# TestRig2.net
KiCad netlist of a schematic drawn in EAGLE
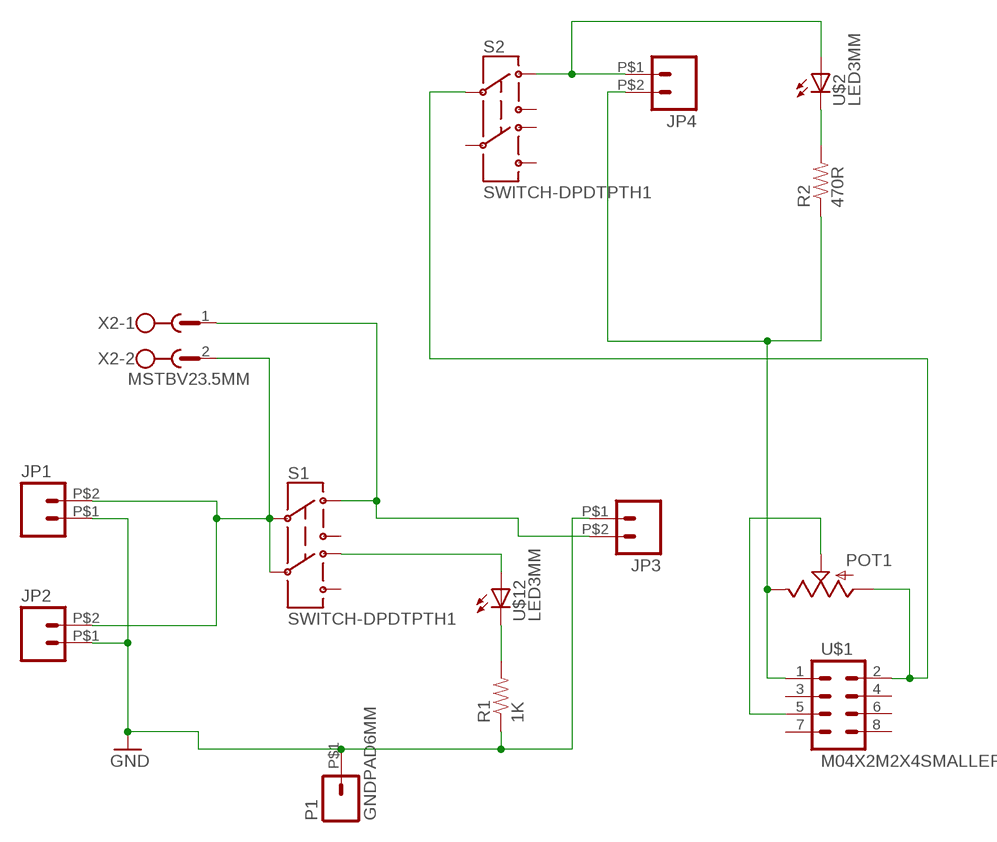
[diagram p0: schematic, sheet 1]

(export (version "E")
  (design (tool "Eeschema 10.0.6"))
  (components
    (comp (ref "JP1")
      (value "M02PTH2")
      (footprint "eagle-import:1X02_BIG")
      (libsource (lib "eagle-import") (part "M02PTH2"))
    )
    (comp (ref "JP2")
      (value "M02PTH2")
      (footprint "eagle-import:1X02_BIG")
      (libsource (lib "eagle-import") (part "M02PTH2"))
    )
    (comp (ref "JP3")
      (value "M02PTH2")
      (footprint "eagle-import:1X02_BIG")
      (libsource (lib "eagle-import") (part "M02PTH2"))
    )
    (comp (ref "JP4")
      (value "M02PTH2")
      (footprint "eagle-import:1X02_BIG")
      (libsource (lib "eagle-import") (part "M02PTH2"))
    )
    (comp (ref "P1")
      (value "GNDPAD6MM")
      (footprint "eagle-import:3.2MMPAD6MM")
      (libsource (lib "eagle-import") (part "GNDPAD6MM"))
    )
    (comp (ref "POT1")
      (value "POT")
      (footprint "eagle-import:ALPS_POT")
      (libsource (lib "eagle-import") (part "POT"))
    )
    (comp (ref "R1")
      (value "1K")
      (footprint "eagle-import:0603-RES")
      (libsource (lib "eagle-import") (part "RESISTOR0603-RES"))
    )
    (comp (ref "R2")
      (value "470R")
      (footprint "eagle-import:0603-RES")
      (libsource (lib "eagle-import") (part "RESISTOR0603-RES"))
    )
    (comp (ref "S1")
      (value "SWITCH-DPDTPTH1")
      (footprint "eagle-import:TECONNECTIVITY-DPDT")
      (libsource (lib "eagle-import") (part "SWITCH-DPDTPTH1"))
    )
    (comp (ref "S2")
      (value "SWITCH-DPDTPTH1")
      (footprint "eagle-import:TECONNECTIVITY-DPDT")
      (libsource (lib "eagle-import") (part "SWITCH-DPDTPTH1"))
    )
    (comp (ref "U$1")
      (value "M04X2M2X4SMALLER")
      (footprint "eagle-import:M2X4SMALLER")
      (libsource (lib "eagle-import") (part "M04X2M2X4SMALLER"))
    )
    (comp (ref "U$2")
      (value "LED3MM")
      (footprint "eagle-import:LED3MM")
      (libsource (lib "eagle-import") (part "LED3MM"))
    )
    (comp (ref "U$12")
      (value "LED3MM")
      (footprint "eagle-import:LED3MM")
      (libsource (lib "eagle-import") (part "LED3MM"))
    )
    (comp (ref "X2")
      (value "MSTBV23.5MM")
      (footprint "eagle-import:MSTBV2-3.5")
      (libsource (lib "eagle-import") (part "MSTBV23.5MM"))
    )
  )
  (nets
    (net (code "1") (name "GND") (class "Default")
      (node (ref "JP1") (pin "P$1") (pinfunction "1_P$1") (pintype "passive"))
      (node (ref "JP2") (pin "P$1") (pinfunction "1_P$1") (pintype "passive"))
      (node (ref "JP3") (pin "P$1") (pinfunction "1_P$1") (pintype "passive"))
      (node (ref "P1") (pin "P$1") (pinfunction "1_P$1") (pintype "passive"))
      (node (ref "R1") (pin "1") (pinfunction "1_1") (pintype "passive"))
    )
    (net (code "2") (name "Net-(JP1-2)") (class "Default")
      (node (ref "JP1") (pin "P$2") (pinfunction "2_P$2") (pintype "passive"))
      (node (ref "JP2") (pin "P$2") (pinfunction "2_P$2") (pintype "passive"))
      (node (ref "S1") (pin "P$2") (pinfunction "2_P$2") (pintype "bidirectional"))
      (node (ref "S1") (pin "P$5") (pinfunction "5_P$5") (pintype "bidirectional"))
      (node (ref "X2") (pin "2") (pinfunction "1_2") (pintype "passive"))
    )
    (net (code "3") (name "Net-(JP3-2)") (class "Default")
      (node (ref "JP3") (pin "P$2") (pinfunction "2_P$2") (pintype "passive"))
      (node (ref "S1") (pin "P$1") (pinfunction "1_P$1") (pintype "bidirectional"))
      (node (ref "X2") (pin "1") (pinfunction "1_1") (pintype "passive"))
    )
    (net (code "4") (name "Net-(JP4-1)") (class "Default")
      (node (ref "JP4") (pin "P$1") (pinfunction "1_P$1") (pintype "passive"))
      (node (ref "S2") (pin "P$1") (pinfunction "1_P$1") (pintype "bidirectional"))
      (node (ref "U$2") (pin "A") (pinfunction "A_A") (pintype "passive"))
    )
    (net (code "5") (name "Net-(JP4-2)") (class "Default")
      (node (ref "JP4") (pin "P$2") (pinfunction "2_P$2") (pintype "passive"))
      (node (ref "POT1") (pin "P$1") (pinfunction "E_P$1") (pintype "passive"))
      (node (ref "R2") (pin "1") (pinfunction "1_1") (pintype "passive"))
      (node (ref "U$1") (pin "1") (pinfunction "1_1") (pintype "passive"))
    )
    (net (code "6") (name "Net-(POT1-A)") (class "Default")
      (node (ref "POT1") (pin "P$3") (pinfunction "A_P$3") (pintype "passive"))
      (node (ref "S2") (pin "P$2") (pinfunction "2_P$2") (pintype "bidirectional"))
      (node (ref "U$1") (pin "2") (pinfunction "2_2") (pintype "passive"))
    )
    (net (code "7") (name "Net-(POT1-S)") (class "Default")
      (node (ref "POT1") (pin "P$2") (pinfunction "S_P$2") (pintype "passive"))
      (node (ref "U$1") (pin "5") (pinfunction "5_5") (pintype "passive"))
    )
    (net (code "8") (name "Net-(S1-4)") (class "Default")
      (node (ref "S1") (pin "P$4") (pinfunction "4_P$4") (pintype "bidirectional"))
      (node (ref "U$12") (pin "A") (pinfunction "A_A") (pintype "passive"))
    )
    (net (code "9") (name "Net-(U$2-C)") (class "Default")
      (node (ref "R2") (pin "2") (pinfunction "2_2") (pintype "passive"))
      (node (ref "U$2") (pin "K") (pinfunction "C_K") (pintype "passive"))
    )
    (net (code "10") (name "Net-(U$12-C)") (class "Default")
      (node (ref "R1") (pin "2") (pinfunction "2_2") (pintype "passive"))
      (node (ref "U$12") (pin "K") (pinfunction "C_K") (pintype "passive"))
    )
    (net (code "11") (name "unconnected-(S1-3-PadP$3)") (class "Default")
      (node (ref "S1") (pin "P$3") (pinfunction "3_P$3") (pintype "bidirectional"))
    )
    (net (code "12") (name "unconnected-(S1-6-PadP$6)") (class "Default")
      (node (ref "S1") (pin "P$6") (pinfunction "6_P$6") (pintype "bidirectional"))
    )
    (net (code "13") (name "unconnected-(S2-3-PadP$3)") (class "Default")
      (node (ref "S2") (pin "P$3") (pinfunction "3_P$3") (pintype "bidirectional"))
    )
    (net (code "14") (name "unconnected-(S2-4-PadP$4)") (class "Default")
      (node (ref "S2") (pin "P$4") (pinfunction "4_P$4") (pintype "bidirectional"))
    )
    (net (code "15") (name "unconnected-(S2-5-PadP$5)") (class "Default")
      (node (ref "S2") (pin "P$5") (pinfunction "5_P$5") (pintype "bidirectional"))
    )
    (net (code "16") (name "unconnected-(S2-6-PadP$6)") (class "Default")
      (node (ref "S2") (pin "P$6") (pinfunction "6_P$6") (pintype "bidirectional"))
    )
    (net (code "17") (name "unconnected-(U$1-Pad3)") (class "Default")
      (node (ref "U$1") (pin "3") (pinfunction "3_3") (pintype "passive"))
    )
    (net (code "18") (name "unconnected-(U$1-Pad4)") (class "Default")
      (node (ref "U$1") (pin "4") (pinfunction "4_4") (pintype "passive"))
    )
    (net (code "19") (name "unconnected-(U$1-Pad6)") (class "Default")
      (node (ref "U$1") (pin "6") (pinfunction "6_6") (pintype "passive"))
    )
    (net (code "20") (name "unconnected-(U$1-Pad7)") (class "Default")
      (node (ref "U$1") (pin "7") (pinfunction "7_7") (pintype "passive"))
    )
    (net (code "21") (name "unconnected-(U$1-Pad8)") (class "Default")
      (node (ref "U$1") (pin "8") (pinfunction "8_8") (pintype "passive"))
    )
  )
)
